# snowflake-v2.net
KiCad netlist of a schematic drawn in EAGLE
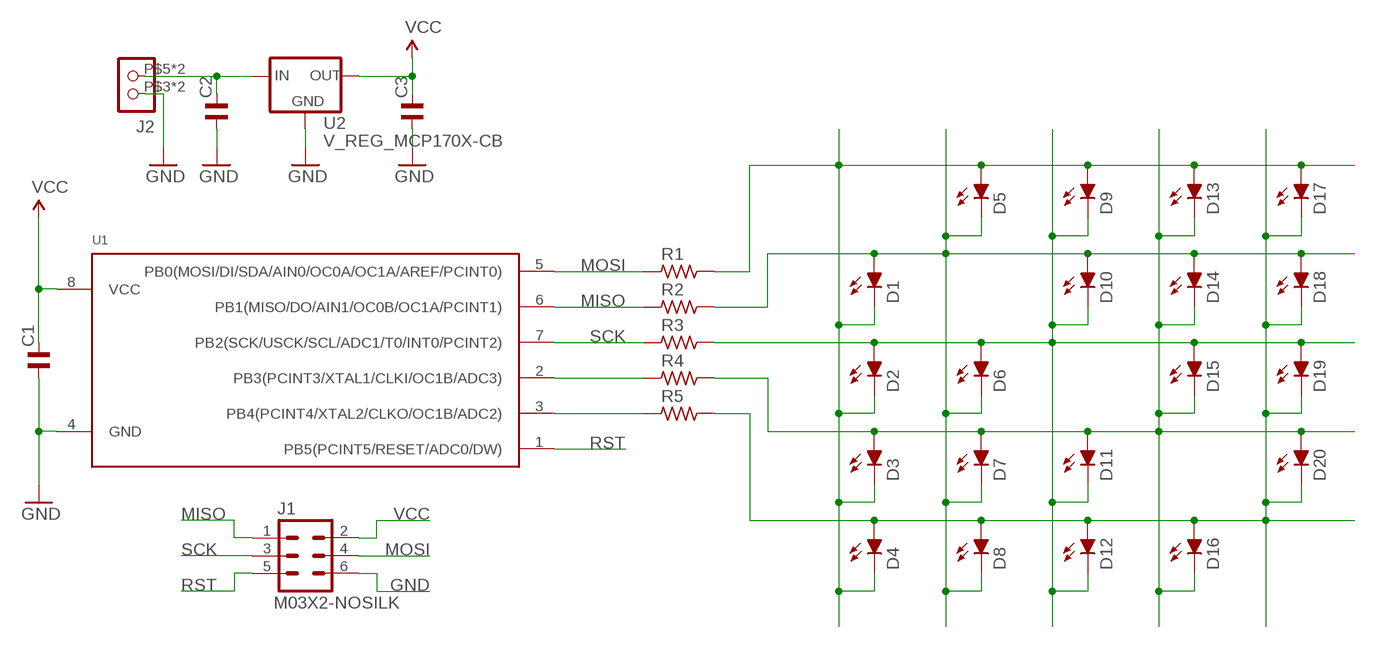
[diagram p0: schematic, sheet 1]

(export (version "E")
  (design (tool "Eeschema 10.0.6"))
  (components
    (comp (ref "C1")
      (value "C_0805NOSILK")
      (footprint "eagle-import:C0805NOSILK")
      (libsource (lib "eagle-import") (part "C_0805NOSILK"))
    )
    (comp (ref "C2")
      (value "C_0805NOSILK")
      (footprint "eagle-import:C0805NOSILK")
      (libsource (lib "eagle-import") (part "C_0805NOSILK"))
    )
    (comp (ref "C3")
      (value "C_0805NOSILK")
      (footprint "eagle-import:C0805NOSILK")
      (libsource (lib "eagle-import") (part "C_0805NOSILK"))
    )
    (comp (ref "D1")
      (value "LEDCHIP-LED0805NOSILK")
      (footprint "eagle-import:CHIP-LED0805NOSILK")
      (libsource (lib "eagle-import") (part "LEDCHIP-LED0805NOSILK"))
    )
    (comp (ref "D2")
      (value "LEDCHIP-LED0805NOSILK")
      (footprint "eagle-import:CHIP-LED0805NOSILK")
      (libsource (lib "eagle-import") (part "LEDCHIP-LED0805NOSILK"))
    )
    (comp (ref "D3")
      (value "LEDCHIP-LED0805NOSILK")
      (footprint "eagle-import:CHIP-LED0805NOSILK")
      (libsource (lib "eagle-import") (part "LEDCHIP-LED0805NOSILK"))
    )
    (comp (ref "D4")
      (value "LEDCHIP-LED0805NOSILK")
      (footprint "eagle-import:CHIP-LED0805NOSILK")
      (libsource (lib "eagle-import") (part "LEDCHIP-LED0805NOSILK"))
    )
    (comp (ref "D5")
      (value "LEDCHIP-LED0805NOSILK")
      (footprint "eagle-import:CHIP-LED0805NOSILK")
      (libsource (lib "eagle-import") (part "LEDCHIP-LED0805NOSILK"))
    )
    (comp (ref "D6")
      (value "LEDCHIP-LED0805NOSILK")
      (footprint "eagle-import:CHIP-LED0805NOSILK")
      (libsource (lib "eagle-import") (part "LEDCHIP-LED0805NOSILK"))
    )
    (comp (ref "D7")
      (value "LEDCHIP-LED0805NOSILK")
      (footprint "eagle-import:CHIP-LED0805NOSILK")
      (libsource (lib "eagle-import") (part "LEDCHIP-LED0805NOSILK"))
    )
    (comp (ref "D8")
      (value "LEDCHIP-LED0805NOSILK")
      (footprint "eagle-import:CHIP-LED0805NOSILK")
      (libsource (lib "eagle-import") (part "LEDCHIP-LED0805NOSILK"))
    )
    (comp (ref "D9")
      (value "LEDCHIP-LED0805NOSILK")
      (footprint "eagle-import:CHIP-LED0805NOSILK")
      (libsource (lib "eagle-import") (part "LEDCHIP-LED0805NOSILK"))
    )
    (comp (ref "D10")
      (value "LEDCHIP-LED0805NOSILK")
      (footprint "eagle-import:CHIP-LED0805NOSILK")
      (libsource (lib "eagle-import") (part "LEDCHIP-LED0805NOSILK"))
    )
    (comp (ref "D11")
      (value "LEDCHIP-LED0805NOSILK")
      (footprint "eagle-import:CHIP-LED0805NOSILK")
      (libsource (lib "eagle-import") (part "LEDCHIP-LED0805NOSILK"))
    )
    (comp (ref "D12")
      (value "LEDCHIP-LED0805NOSILK")
      (footprint "eagle-import:CHIP-LED0805NOSILK")
      (libsource (lib "eagle-import") (part "LEDCHIP-LED0805NOSILK"))
    )
    (comp (ref "D13")
      (value "LEDCHIP-LED0805NOSILK")
      (footprint "eagle-import:CHIP-LED0805NOSILK")
      (libsource (lib "eagle-import") (part "LEDCHIP-LED0805NOSILK"))
    )
    (comp (ref "D14")
      (value "LEDCHIP-LED0805NOSILK")
      (footprint "eagle-import:CHIP-LED0805NOSILK")
      (libsource (lib "eagle-import") (part "LEDCHIP-LED0805NOSILK"))
    )
    (comp (ref "D15")
      (value "LEDCHIP-LED0805NOSILK")
      (footprint "eagle-import:CHIP-LED0805NOSILK")
      (libsource (lib "eagle-import") (part "LEDCHIP-LED0805NOSILK"))
    )
    (comp (ref "D16")
      (value "LEDCHIP-LED0805NOSILK")
      (footprint "eagle-import:CHIP-LED0805NOSILK")
      (libsource (lib "eagle-import") (part "LEDCHIP-LED0805NOSILK"))
    )
    (comp (ref "D17")
      (value "LEDCHIP-LED0805NOSILK")
      (footprint "eagle-import:CHIP-LED0805NOSILK")
      (libsource (lib "eagle-import") (part "LEDCHIP-LED0805NOSILK"))
    )
    (comp (ref "D18")
      (value "LEDCHIP-LED0805NOSILK")
      (footprint "eagle-import:CHIP-LED0805NOSILK")
      (libsource (lib "eagle-import") (part "LEDCHIP-LED0805NOSILK"))
    )
    (comp (ref "D19")
      (value "LEDCHIP-LED0805NOSILK")
      (footprint "eagle-import:CHIP-LED0805NOSILK")
      (libsource (lib "eagle-import") (part "LEDCHIP-LED0805NOSILK"))
    )
    (comp (ref "D20")
      (value "LEDCHIP-LED0805NOSILK")
      (footprint "eagle-import:CHIP-LED0805NOSILK")
      (libsource (lib "eagle-import") (part "LEDCHIP-LED0805NOSILK"))
    )
    (comp (ref "J1")
      (value "M03X2-NOSILK")
      (footprint "eagle-import:2X03_LOCK_NOSILK")
      (libsource (lib "eagle-import") (part "M03X2-NOSILK"))
    )
    (comp (ref "J2")
      (value "CON_TERMINAL_HOLES")
      (footprint "eagle-import:TERMINAL_2P_4H")
      (libsource (lib "eagle-import") (part "CON_TERMINAL_HOLES"))
    )
    (comp (ref "R1")
      (value "R_0805NOSILK")
      (footprint "eagle-import:R0805NOSILK")
      (libsource (lib "eagle-import") (part "R_0805NOSILK"))
    )
    (comp (ref "R2")
      (value "R_0805NOSILK")
      (footprint "eagle-import:R0805NOSILK")
      (libsource (lib "eagle-import") (part "R_0805NOSILK"))
    )
    (comp (ref "R3")
      (value "R_0805NOSILK")
      (footprint "eagle-import:R0805NOSILK")
      (libsource (lib "eagle-import") (part "R_0805NOSILK"))
    )
    (comp (ref "R4")
      (value "R_0805NOSILK")
      (footprint "eagle-import:R0805NOSILK")
      (libsource (lib "eagle-import") (part "R_0805NOSILK"))
    )
    (comp (ref "R5")
      (value "R_0805NOSILK")
      (footprint "eagle-import:R0805NOSILK")
      (libsource (lib "eagle-import") (part "R_0805NOSILK"))
    )
    (comp (ref "U1")
      (value "ATTINY5-20SU-NOSILK")
      (footprint "eagle-import:SOP8-8S2-NOSILK")
      (libsource (lib "eagle-import") (part "ATTINY5-20SU-NOSILK"))
    )
    (comp (ref "U2")
      (value "V_REG_MCP170X-CB")
      (footprint "eagle-import:SOT23")
      (libsource (lib "eagle-import") (part "V_REG_MCP170X-CB"))
    )
  )
  (nets
    (net (code "1") (name "/MISO") (class "Default")
      (node (ref "J1") (pin "1") (pinfunction "1_1") (pintype "passive"))
      (node (ref "R2") (pin "1") (pinfunction "1_1") (pintype "passive"))
      (node (ref "U1") (pin "6") (pinfunction "PB1(MISO/DO/AIN1/OC0B/OC1A/PCINT1)_6") (pintype "bidirectional"))
    )
    (net (code "2") (name "/MOSI") (class "Default")
      (node (ref "J1") (pin "4") (pinfunction "4_4") (pintype "passive"))
      (node (ref "R1") (pin "1") (pinfunction "1_1") (pintype "passive"))
      (node (ref "U1") (pin "5") (pinfunction "PB0(MOSI/DI/SDA/AIN0/OC0A/OC1A/AREF/PCINT0)_5") (pintype "bidirectional"))
    )
    (net (code "3") (name "/RST") (class "Default")
      (node (ref "J1") (pin "5") (pinfunction "5_5") (pintype "passive"))
      (node (ref "U1") (pin "1") (pinfunction "PB5(PCINT5/RESET/ADC0/DW)_1") (pintype "bidirectional"))
    )
    (net (code "4") (name "/SCK") (class "Default")
      (node (ref "J1") (pin "3") (pinfunction "3_3") (pintype "passive"))
      (node (ref "R3") (pin "1") (pinfunction "1_1") (pintype "passive"))
      (node (ref "U1") (pin "7") (pinfunction "PB2(SCK/USCK/SCL/ADC1/T0/INT0/PCINT2)_7") (pintype "bidirectional"))
    )
    (net (code "5") (name "GND") (class "Default")
      (node (ref "C1") (pin "1") (pinfunction "1_1") (pintype "passive"))
      (node (ref "C2") (pin "1") (pinfunction "1_1") (pintype "passive"))
      (node (ref "C3") (pin "1") (pinfunction "1_1") (pintype "passive"))
      (node (ref "J1") (pin "6") (pinfunction "6_6") (pintype "passive"))
      (node (ref "J2") (pin "P$3") (pinfunction "1_P$3") (pintype "passive"))
      (node (ref "J2") (pin "P$4") (pinfunction "1_P$4") (pintype "passive"))
      (node (ref "U1") (pin "4") (pinfunction "GND_4") (pintype "bidirectional"))
      (node (ref "U2") (pin "1") (pinfunction "GND_1") (pintype "input"))
    )
    (net (code "6") (name "Net-(D1-PadA)") (class "Default")
      (node (ref "D1") (pin "A") (pinfunction "A_A") (pintype "passive"))
      (node (ref "D10") (pin "A") (pinfunction "A_A") (pintype "passive"))
      (node (ref "D14") (pin "A") (pinfunction "A_A") (pintype "passive"))
      (node (ref "D18") (pin "A") (pinfunction "A_A") (pintype "passive"))
      (node (ref "D5") (pin "C") (pinfunction "C_C") (pintype "passive"))
      (node (ref "D6") (pin "C") (pinfunction "C_C") (pintype "passive"))
      (node (ref "D7") (pin "C") (pinfunction "C_C") (pintype "passive"))
      (node (ref "D8") (pin "C") (pinfunction "C_C") (pintype "passive"))
      (node (ref "R2") (pin "2") (pinfunction "2_2") (pintype "passive"))
    )
    (net (code "7") (name "Net-(D1-PadC)") (class "Default")
      (node (ref "D1") (pin "C") (pinfunction "C_C") (pintype "passive"))
      (node (ref "D13") (pin "A") (pinfunction "A_A") (pintype "passive"))
      (node (ref "D17") (pin "A") (pinfunction "A_A") (pintype "passive"))
      (node (ref "D2") (pin "C") (pinfunction "C_C") (pintype "passive"))
      (node (ref "D3") (pin "C") (pinfunction "C_C") (pintype "passive"))
      (node (ref "D4") (pin "C") (pinfunction "C_C") (pintype "passive"))
      (node (ref "D5") (pin "A") (pinfunction "A_A") (pintype "passive"))
      (node (ref "D9") (pin "A") (pinfunction "A_A") (pintype "passive"))
      (node (ref "R1") (pin "2") (pinfunction "2_2") (pintype "passive"))
    )
    (net (code "8") (name "Net-(D10-PadC)") (class "Default")
      (node (ref "D10") (pin "C") (pinfunction "C_C") (pintype "passive"))
      (node (ref "D11") (pin "C") (pinfunction "C_C") (pintype "passive"))
      (node (ref "D12") (pin "C") (pinfunction "C_C") (pintype "passive"))
      (node (ref "D15") (pin "A") (pinfunction "A_A") (pintype "passive"))
      (node (ref "D19") (pin "A") (pinfunction "A_A") (pintype "passive"))
      (node (ref "D2") (pin "A") (pinfunction "A_A") (pintype "passive"))
      (node (ref "D6") (pin "A") (pinfunction "A_A") (pintype "passive"))
      (node (ref "D9") (pin "C") (pinfunction "C_C") (pintype "passive"))
      (node (ref "R3") (pin "2") (pinfunction "2_2") (pintype "passive"))
    )
    (net (code "9") (name "Net-(D11-PadA)") (class "Default")
      (node (ref "D11") (pin "A") (pinfunction "A_A") (pintype "passive"))
      (node (ref "D13") (pin "C") (pinfunction "C_C") (pintype "passive"))
      (node (ref "D14") (pin "C") (pinfunction "C_C") (pintype "passive"))
      (node (ref "D15") (pin "C") (pinfunction "C_C") (pintype "passive"))
      (node (ref "D16") (pin "C") (pinfunction "C_C") (pintype "passive"))
      (node (ref "D20") (pin "A") (pinfunction "A_A") (pintype "passive"))
      (node (ref "D3") (pin "A") (pinfunction "A_A") (pintype "passive"))
      (node (ref "D7") (pin "A") (pinfunction "A_A") (pintype "passive"))
      (node (ref "R4") (pin "2") (pinfunction "2_2") (pintype "passive"))
    )
    (net (code "10") (name "Net-(D12-PadA)") (class "Default")
      (node (ref "D12") (pin "A") (pinfunction "A_A") (pintype "passive"))
      (node (ref "D16") (pin "A") (pinfunction "A_A") (pintype "passive"))
      (node (ref "D17") (pin "C") (pinfunction "C_C") (pintype "passive"))
      (node (ref "D18") (pin "C") (pinfunction "C_C") (pintype "passive"))
      (node (ref "D19") (pin "C") (pinfunction "C_C") (pintype "passive"))
      (node (ref "D20") (pin "C") (pinfunction "C_C") (pintype "passive"))
      (node (ref "D4") (pin "A") (pinfunction "A_A") (pintype "passive"))
      (node (ref "D8") (pin "A") (pinfunction "A_A") (pintype "passive"))
      (node (ref "R5") (pin "2") (pinfunction "2_2") (pintype "passive"))
    )
    (net (code "11") (name "Net-(U1-PB3(PCINT3{slash}XTAL1{slash}CLKI{slash}OC1B{slash}ADC3))") (class "Default")
      (node (ref "R4") (pin "1") (pinfunction "1_1") (pintype "passive"))
      (node (ref "U1") (pin "2") (pinfunction "PB3(PCINT3/XTAL1/CLKI/OC1B/ADC3)_2") (pintype "bidirectional"))
    )
    (net (code "12") (name "Net-(U1-PB4(PCINT4{slash}XTAL2{slash}CLKO{slash}OC1B{slash}ADC2))") (class "Default")
      (node (ref "R5") (pin "1") (pinfunction "1_1") (pintype "passive"))
      (node (ref "U1") (pin "3") (pinfunction "PB4(PCINT4/XTAL2/CLKO/OC1B/ADC2)_3") (pintype "bidirectional"))
    )
    (net (code "13") (name "Net-(U2-IN)") (class "Default")
      (node (ref "C2") (pin "2") (pinfunction "2_2") (pintype "passive"))
      (node (ref "J2") (pin "P$5") (pinfunction "2_P$5") (pintype "passive"))
      (node (ref "J2") (pin "P$6") (pinfunction "2_P$6") (pintype "passive"))
      (node (ref "U2") (pin "3") (pinfunction "IN_3") (pintype "input"))
    )
    (net (code "14") (name "VCC") (class "Default")
      (node (ref "C1") (pin "2") (pinfunction "2_2") (pintype "passive"))
      (node (ref "C3") (pin "2") (pinfunction "2_2") (pintype "passive"))
      (node (ref "J1") (pin "2") (pinfunction "2_2") (pintype "passive"))
      (node (ref "U1") (pin "8") (pinfunction "VCC_8") (pintype "bidirectional"))
      (node (ref "U2") (pin "2") (pinfunction "OUT_2") (pintype "power_in"))
    )
  )
)
